# SW6208_A_A_B_C_L_LED__188.net
KiCad netlist of a schematic drawn in Altium Designer
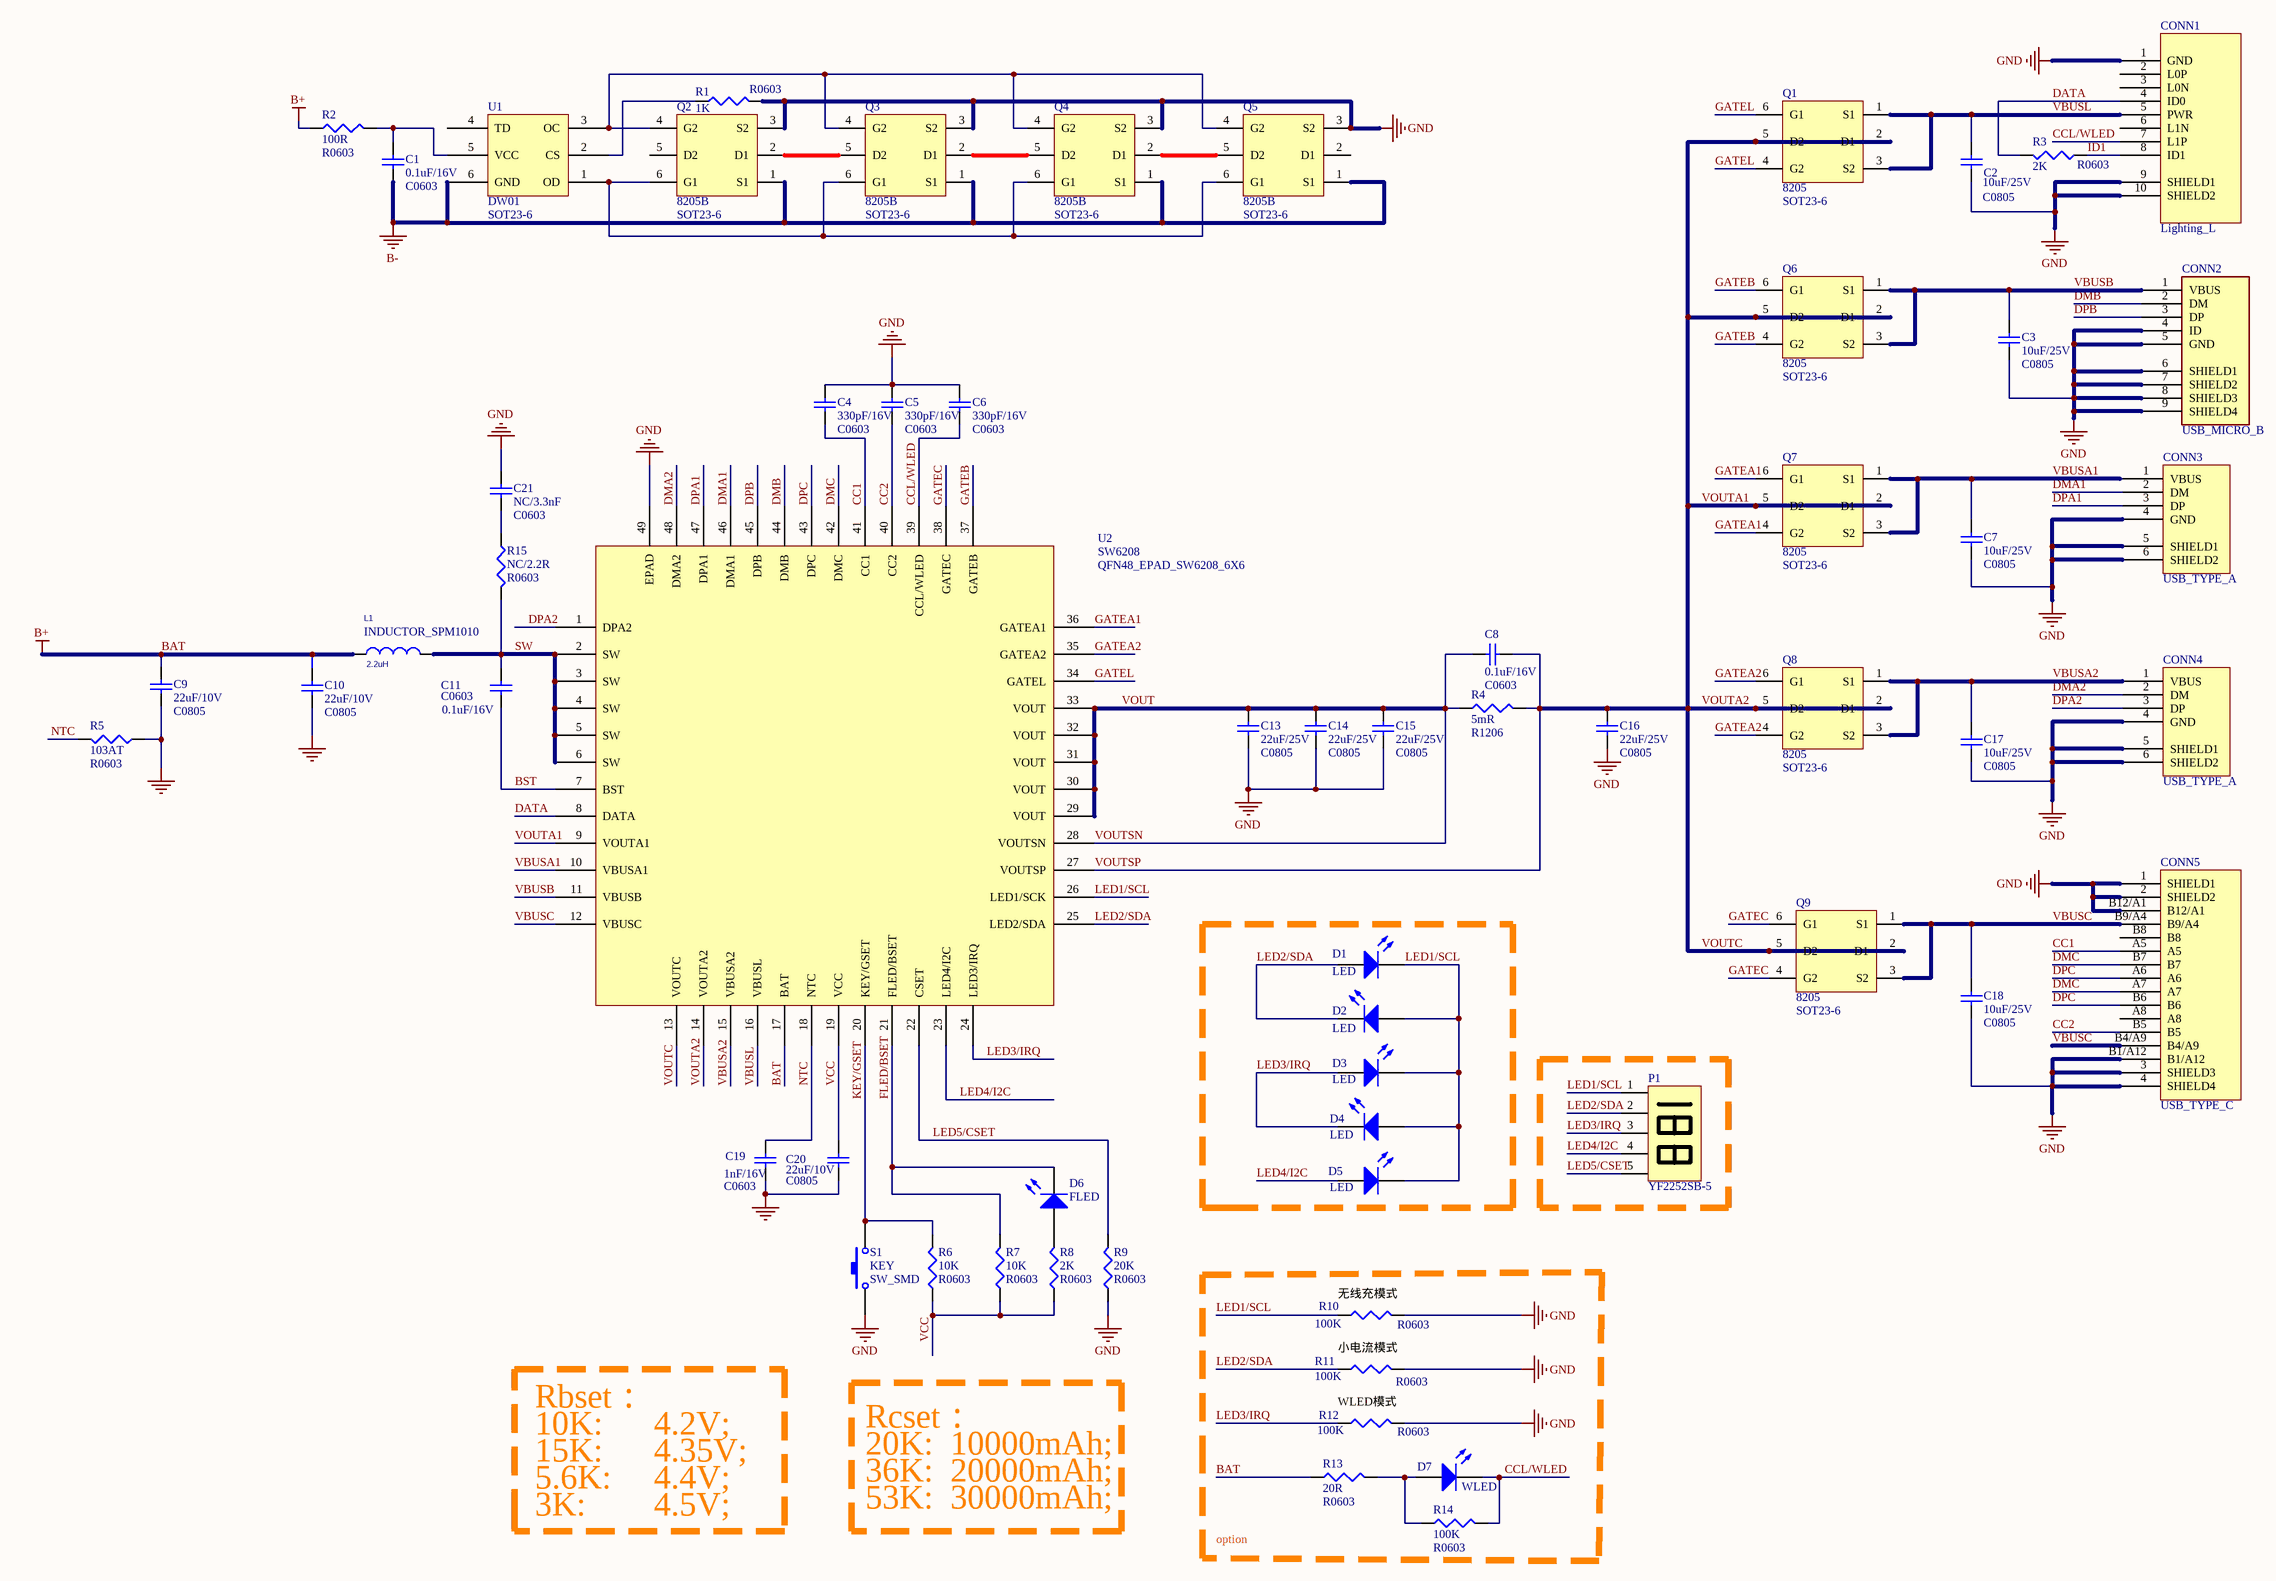
[diagram p0: SW6208+A+A+B+C+L+LED_普通188数码管.SchDoc]

(export (version "E")
  (design (tool "Eeschema 10.0.6"))
  (components
    (comp (ref "C1")
      (value "0.1uF/16V")
      (footprint "C0603")
      (description "Capacitor")
      (fields (field (name "PUBLISHER") "Altium Limited"))
      (libsource (lib "参考设计器件原理图更新") (part "CAP0603"))
    )
    (comp (ref "C2")
      (value "10uF/25V")
      (footprint "C0805")
      (description "Capacitor")
      (fields (field (name "PUBLISHER") "Altium Limited"))
      (libsource (lib "参考设计器件原理图更新") (part "CAP0805"))
    )
    (comp (ref "C3")
      (value "10uF/25V")
      (footprint "C0805")
      (description "Capacitor")
      (fields (field (name "PUBLISHER") "Altium Limited"))
      (libsource (lib "参考设计器件原理图更新") (part "CAP0805"))
    )
    (comp (ref "C4")
      (value "330pF/16V")
      (footprint "C0603")
      (description "Capacitor")
      (fields (field (name "PUBLISHER") "Altium Limited"))
      (libsource (lib "参考设计器件原理图更新") (part "CAP0603"))
    )
    (comp (ref "C5")
      (value "330pF/16V")
      (footprint "C0603")
      (description "Capacitor")
      (fields (field (name "PUBLISHER") "Altium Limited"))
      (libsource (lib "参考设计器件原理图更新") (part "CAP0603"))
    )
    (comp (ref "C6")
      (value "330pF/16V")
      (footprint "C0603")
      (description "Capacitor")
      (fields (field (name "PUBLISHER") "Altium Limited"))
      (libsource (lib "参考设计器件原理图更新") (part "CAP0603"))
    )
    (comp (ref "C7")
      (value "10uF/25V")
      (footprint "C0805")
      (description "Capacitor")
      (fields (field (name "PUBLISHER") "Altium Limited"))
      (libsource (lib "参考设计器件原理图更新") (part "CAP0805"))
    )
    (comp (ref "C8")
      (value "0.1uF/16V")
      (footprint "C0603")
      (description "Capacitor")
      (fields (field (name "PUBLISHER") "Altium Limited"))
      (libsource (lib "参考设计器件原理图更新") (part "CAP0603"))
    )
    (comp (ref "C9")
      (value "22uF/10V")
      (footprint "C0805")
      (description "Capacitor")
      (fields (field (name "PUBLISHER") "Altium Limited"))
      (libsource (lib "参考设计器件原理图更新") (part "CAP0805"))
    )
    (comp (ref "C10")
      (value "22uF/10V")
      (footprint "C0805")
      (description "Capacitor")
      (fields (field (name "PUBLISHER") "Altium Limited"))
      (libsource (lib "参考设计器件原理图更新") (part "CAP0805"))
    )
    (comp (ref "C11")
      (value "0.1uF/16V")
      (footprint "C0603")
      (description "Capacitor")
      (fields (field (name "PUBLISHER") "Altium Limited"))
      (libsource (lib "参考设计器件原理图更新") (part "CAP0603"))
    )
    (comp (ref "C13")
      (value "22uF/25V")
      (footprint "C0805")
      (description "Capacitor")
      (fields (field (name "PUBLISHER") "Altium Limited"))
      (libsource (lib "参考设计器件原理图更新") (part "CAP0805"))
    )
    (comp (ref "C14")
      (value "22uF/25V")
      (footprint "C0805")
      (description "Capacitor")
      (fields (field (name "PUBLISHER") "Altium Limited"))
      (libsource (lib "参考设计器件原理图更新") (part "CAP0805"))
    )
    (comp (ref "C15")
      (value "22uF/25V")
      (footprint "C0805")
      (description "Capacitor")
      (fields (field (name "PUBLISHER") "Altium Limited"))
      (libsource (lib "参考设计器件原理图更新") (part "CAP0805"))
    )
    (comp (ref "C16")
      (value "22uF/25V")
      (footprint "C0805")
      (description "Capacitor")
      (fields (field (name "PUBLISHER") "Altium Limited"))
      (libsource (lib "参考设计器件原理图更新") (part "CAP0805"))
    )
    (comp (ref "C17")
      (value "10uF/25V")
      (footprint "C0805")
      (description "Capacitor")
      (fields (field (name "PUBLISHER") "Altium Limited"))
      (libsource (lib "参考设计器件原理图更新") (part "CAP0805"))
    )
    (comp (ref "C18")
      (value "10uF/25V")
      (footprint "C0805")
      (description "Capacitor")
      (fields (field (name "PUBLISHER") "Altium Limited"))
      (libsource (lib "参考设计器件原理图更新") (part "CAP0805"))
    )
    (comp (ref "C19")
      (value "1nF/16V")
      (footprint "C0603")
      (description "Capacitor")
      (fields (field (name "PUBLISHER") "Altium Limited"))
      (libsource (lib "参考设计器件原理图更新") (part "CAP0603"))
    )
    (comp (ref "C20")
      (value "22uF/10V")
      (footprint "C0805")
      (description "Capacitor")
      (fields (field (name "PUBLISHER") "Altium Limited"))
      (libsource (lib "参考设计器件原理图更新") (part "CAP0805"))
    )
    (comp (ref "C21")
      (value "NC/3.3nF")
      (footprint "C0603")
      (description "Capacitor")
      (fields (field (name "PUBLISHER") "Altium Limited"))
      (libsource (lib "参考设计器件原理图更新") (part "CAP0603"))
    )
    (comp (ref "CONN1")
      (value "Lighting_L")
      (footprint "Lighting")
      (libsource (lib "参考设计器件原理图更新") (part "LIGHTING_PORT"))
    )
    (comp (ref "CONN2")
      (value "USB_MICRO_B")
      (footprint "USB_MICRO_B")
      (libsource (lib "参考设计器件原理图更新") (part "USB_MICRO_B"))
    )
    (comp (ref "CONN3")
      (value "USB_TYPE_A")
      (footprint "USB_TYPE_A")
      (libsource (lib "参考设计器件原理图更新") (part "USB_TYPE_A"))
    )
    (comp (ref "CONN4")
      (value "USB_TYPE_A")
      (footprint "USB_TYPE_A")
      (libsource (lib "参考设计器件原理图更新") (part "USB_TYPE_A"))
    )
    (comp (ref "CONN5")
      (value "USB_TYPE_C")
      (footprint "LOUISAD:USB_TYPE_C")
      (libsource (lib "参考设计器件原理图更新") (part "USB_TYPE_C"))
    )
    (comp (ref "D1")
      (value "LED")
      (footprint "LED0603")
      (fields (field (name "PUBLISHER") "Altium Limited"))
      (libsource (lib "参考设计器件原理图更新") (part "LED_0603"))
    )
    (comp (ref "D2")
      (value "LED")
      (footprint "LED0603")
      (fields (field (name "PUBLISHER") "Altium Limited"))
      (libsource (lib "参考设计器件原理图更新") (part "LED_0603"))
    )
    (comp (ref "D3")
      (value "LED")
      (footprint "LED0603")
      (fields (field (name "PUBLISHER") "Altium Limited"))
      (libsource (lib "参考设计器件原理图更新") (part "LED_0603"))
    )
    (comp (ref "D4")
      (value "LED")
      (footprint "LED0603")
      (fields (field (name "PUBLISHER") "Altium Limited"))
      (libsource (lib "参考设计器件原理图更新") (part "LED_0603"))
    )
    (comp (ref "D5")
      (value "LED")
      (footprint "LED0603")
      (fields (field (name "PUBLISHER") "Altium Limited"))
      (libsource (lib "参考设计器件原理图更新") (part "LED_0603"))
    )
    (comp (ref "D6")
      (value "FLED")
      (footprint "LED0603")
      (description "LED")
      (fields (field (name "PUBLISHER") "Altium Limited"))
      (libsource (lib "参考设计器件原理图更新") (part "LED_0603"))
    )
    (comp (ref "D7")
      (value "WLED")
      (footprint "LED_5MM")
      (fields (field (name "PUBLISHER") "Altium Limited"))
      (libsource (lib "参考设计器件原理图更新") (part "WLED"))
    )
    (comp (ref "L1")
      (value "2.2uH")
      (footprint "INDUCTOR_SPM1010")
      (description "INDUCTOR")
      (libsource (lib "参考设计器件原理图更新") (part "INDUCTOR_SPM1010"))
    )
    (comp (ref "P1")
      (value "YF2252SB-5")
      (footprint "LED_Display_5")
      (description "188_LED_Display")
      (libsource (lib "参考设计器件原理图更新") (part "LED_Display_5"))
    )
    (comp (ref "Q1")
      (value "8205")
      (footprint "SOT23-6")
      (description "NMOS")
      (fields (field (name "FOOTPRINF") "SOT23-6"))
      (libsource (lib "") (part "8205_1"))
    )
    (comp (ref "Q2")
      (value "8205B")
      (footprint "SOT23-6")
      (description "NMOS")
      (fields (field (name "FOOTPRINF") "SOT23-6"))
      (libsource (lib "参考设计器件原理图更新") (part "8205"))
    )
    (comp (ref "Q3")
      (value "8205B")
      (footprint "SOT23-6")
      (description "NMOS")
      (fields (field (name "FOOTPRINF") "SOT23-6"))
      (libsource (lib "参考设计器件原理图更新") (part "8205"))
    )
    (comp (ref "Q4")
      (value "8205B")
      (footprint "SOT23-6")
      (description "NMOS")
      (fields (field (name "FOOTPRINF") "SOT23-6"))
      (libsource (lib "参考设计器件原理图更新") (part "8205"))
    )
    (comp (ref "Q5")
      (value "8205B")
      (footprint "SOT23-6")
      (description "NMOS")
      (fields (field (name "FOOTPRINF") "SOT23-6"))
      (libsource (lib "参考设计器件原理图更新") (part "8205"))
    )
    (comp (ref "Q6")
      (value "8205")
      (footprint "SOT23-6")
      (description "NMOS")
      (fields (field (name "FOOTPRINF") "SOT23-6"))
      (libsource (lib "") (part "8205_1"))
    )
    (comp (ref "Q7")
      (value "8205")
      (footprint "SOT23-6")
      (description "NMOS")
      (fields (field (name "FOOTPRINF") "SOT23-6"))
      (libsource (lib "") (part "8205_1"))
    )
    (comp (ref "Q8")
      (value "8205")
      (footprint "SOT23-6")
      (description "NMOS")
      (fields (field (name "FOOTPRINF") "SOT23-6"))
      (libsource (lib "") (part "8205_1"))
    )
    (comp (ref "Q9")
      (value "8205")
      (footprint "SOT23-6")
      (description "NMOS")
      (fields (field (name "FOOTPRINF") "SOT23-6"))
      (libsource (lib "") (part "8205_1"))
    )
    (comp (ref "R1")
      (value "1K")
      (footprint "R0603")
      (description "Resistor")
      (fields (field (name "PUBLISHER") "Altium Limited"))
      (libsource (lib "参考设计器件原理图更新") (part "RES_0603"))
    )
    (comp (ref "R2")
      (value "100R")
      (footprint "R0603")
      (description "Resistor")
      (fields (field (name "PUBLISHER") "Altium Limited"))
      (libsource (lib "参考设计器件原理图更新") (part "RES_0603"))
    )
    (comp (ref "R3")
      (value "2K")
      (footprint "R0603")
      (description "Resistor")
      (fields (field (name "PUBLISHER") "Altium Limited"))
      (libsource (lib "参考设计器件原理图更新") (part "RES_0603"))
    )
    (comp (ref "R4")
      (value "5mR")
      (footprint "R1206")
      (description "Resistor")
      (fields (field (name "PUBLISHER") "Altium Limited"))
      (libsource (lib "参考设计器件原理图更新") (part "RES_1206"))
    )
    (comp (ref "R5")
      (value "103AT")
      (footprint "R0603")
      (description "Resistor")
      (fields (field (name "PUBLISHER") "Altium Limited"))
      (libsource (lib "参考设计器件原理图更新") (part "RES_0603"))
    )
    (comp (ref "R6")
      (value "10K")
      (footprint "R0603")
      (description "Resistor")
      (fields (field (name "PUBLISHER") "Altium Limited"))
      (libsource (lib "参考设计器件原理图更新") (part "RES_0603"))
    )
    (comp (ref "R7")
      (value "10K")
      (footprint "R0603")
      (description "Resistor")
      (fields (field (name "PUBLISHER") "Altium Limited"))
      (libsource (lib "参考设计器件原理图更新") (part "RES_0603"))
    )
    (comp (ref "R8")
      (value "2K")
      (footprint "R0603")
      (description "Resistor")
      (fields (field (name "PUBLISHER") "Altium Limited"))
      (libsource (lib "参考设计器件原理图更新") (part "RES_0603"))
    )
    (comp (ref "R9")
      (value "20K")
      (footprint "R0603")
      (description "Resistor")
      (fields (field (name "PUBLISHER") "Altium Limited"))
      (libsource (lib "参考设计器件原理图更新") (part "RES_0603"))
    )
    (comp (ref "R10")
      (value "100K")
      (footprint "R0603")
      (description "Resistor")
      (fields (field (name "PUBLISHER") "Altium Limited"))
      (libsource (lib "参考设计器件原理图更新") (part "RES_0603"))
    )
    (comp (ref "R11")
      (value "100K")
      (footprint "R0603")
      (description "Resistor")
      (fields (field (name "PUBLISHER") "Altium Limited"))
      (libsource (lib "参考设计器件原理图更新") (part "RES_0603"))
    )
    (comp (ref "R12")
      (value "100K")
      (footprint "R0603")
      (description "Resistor")
      (fields (field (name "PUBLISHER") "Altium Limited"))
      (libsource (lib "参考设计器件原理图更新") (part "RES_0603"))
    )
    (comp (ref "R13")
      (value "20R")
      (footprint "R0603")
      (description "Resistor")
      (fields (field (name "PUBLISHER") "Altium Limited"))
      (libsource (lib "参考设计器件原理图更新") (part "RES_0603"))
    )
    (comp (ref "R14")
      (value "100K")
      (footprint "R0603")
      (description "Resistor")
      (fields (field (name "PUBLISHER") "Altium Limited"))
      (libsource (lib "参考设计器件原理图更新") (part "RES_0603"))
    )
    (comp (ref "R15")
      (value "NC/2.2R")
      (footprint "R0603")
      (description "Resistor")
      (fields (field (name "PUBLISHER") "Altium Limited"))
      (libsource (lib "参考设计器件原理图更新") (part "RES_0603"))
    )
    (comp (ref "S1")
      (value "KEY")
      (footprint "SW_SMD")
      (fields (field (name "FOOTPRINF") "SW_SMD"))
      (libsource (lib "参考设计器件原理图更新") (part "SW K"))
    )
    (comp (ref "U1")
      (value "DW01")
      (footprint "SOT23-6")
      (description "BAT_PROTECT_IC")
      (libsource (lib "参考设计器件原理图更新") (part "DW01"))
    )
    (comp (ref "U2")
      (value "SW6208")
      (footprint "QFN48_EPAD_SW6208_6X6")
      (description "IC")
      (libsource (lib "芯片型号原理图") (part "SW6208"))
    )
  )
  (nets
    (net (code "1") (name "/BST") (class "Default")
      (node (ref "C11") (pin "1") (pinfunction "1_1") (pintype "passive"))
      (node (ref "U2") (pin "7") (pinfunction "BST_7") (pintype "passive"))
    )
    (net (code "2") (name "/CC1") (class "Default")
      (node (ref "C4") (pin "1") (pinfunction "1_1") (pintype "passive"))
      (node (ref "CONN5") (pin "A5") (pinfunction "A5_A5") (pintype "passive"))
      (node (ref "U2") (pin "41") (pinfunction "CC1_41") (pintype "passive"))
    )
    (net (code "3") (name "/CC2") (class "Default")
      (node (ref "C5") (pin "1") (pinfunction "1_1") (pintype "passive"))
      (node (ref "CONN5") (pin "B5") (pinfunction "B5_B5") (pintype "passive"))
      (node (ref "U2") (pin "40") (pinfunction "CC2_40") (pintype "passive"))
    )
    (net (code "4") (name "/CCL{slash}WLED") (class "Default")
      (node (ref "C6") (pin "1") (pinfunction "1_1") (pintype "passive"))
      (node (ref "CONN1") (pin "7") (pinfunction "L1P_7") (pintype "passive"))
      (node (ref "D7") (pin "2") (pinfunction "K_2") (pintype "passive"))
      (node (ref "R14") (pin "2") (pinfunction "2_2") (pintype "passive"))
      (node (ref "U2") (pin "39") (pinfunction "CCL/WLED_39") (pintype "passive"))
    )
    (net (code "5") (name "/DATA") (class "Default")
      (node (ref "CONN1") (pin "4") (pinfunction "ID0_4") (pintype "passive"))
      (node (ref "R3") (pin "2") (pinfunction "2_2") (pintype "passive"))
      (node (ref "U2") (pin "8") (pinfunction "DATA_8") (pintype "passive"))
    )
    (net (code "6") (name "/DMA1") (class "Default")
      (node (ref "CONN3") (pin "2") (pinfunction "DM_2") (pintype "passive"))
      (node (ref "U2") (pin "46") (pinfunction "DMA1_46") (pintype "passive"))
    )
    (net (code "7") (name "/DMA2") (class "Default")
      (node (ref "CONN4") (pin "2") (pinfunction "DM_2") (pintype "passive"))
      (node (ref "U2") (pin "48") (pinfunction "DMA2_48") (pintype "passive"))
    )
    (net (code "8") (name "/DMB") (class "Default")
      (node (ref "CONN2") (pin "2") (pinfunction "DM_2") (pintype "passive"))
      (node (ref "U2") (pin "44") (pinfunction "DMB_44") (pintype "passive"))
    )
    (net (code "9") (name "/DMC") (class "Default")
      (node (ref "CONN5") (pin "A7") (pinfunction "A7_A7") (pintype "passive"))
      (node (ref "CONN5") (pin "B7") (pinfunction "B7_B7") (pintype "passive"))
      (node (ref "U2") (pin "42") (pinfunction "DMC_42") (pintype "passive"))
    )
    (net (code "10") (name "/DPA1") (class "Default")
      (node (ref "CONN3") (pin "3") (pinfunction "DP_3") (pintype "passive"))
      (node (ref "U2") (pin "47") (pinfunction "DPA1_47") (pintype "passive"))
    )
    (net (code "11") (name "/DPA2") (class "Default")
      (node (ref "CONN4") (pin "3") (pinfunction "DP_3") (pintype "passive"))
      (node (ref "U2") (pin "1") (pinfunction "DPA2_1") (pintype "passive"))
    )
    (net (code "12") (name "/DPB") (class "Default")
      (node (ref "CONN2") (pin "3") (pinfunction "DP_3") (pintype "passive"))
      (node (ref "U2") (pin "45") (pinfunction "DPB_45") (pintype "passive"))
    )
    (net (code "13") (name "/DPC") (class "Default")
      (node (ref "CONN5") (pin "A6") (pinfunction "A6_A6") (pintype "passive"))
      (node (ref "CONN5") (pin "B6") (pinfunction "B6_B6") (pintype "passive"))
      (node (ref "U2") (pin "43") (pinfunction "DPC_43") (pintype "passive"))
    )
    (net (code "14") (name "/FLED{slash}BSET") (class "Default")
      (node (ref "D6") (pin "2") (pinfunction "K_2") (pintype "passive"))
      (node (ref "R7") (pin "2") (pinfunction "2_2") (pintype "passive"))
      (node (ref "U2") (pin "21") (pinfunction "FLED/BSET_21") (pintype "passive"))
    )
    (net (code "15") (name "/GATEA1") (class "Default")
      (node (ref "Q7") (pin "4") (pinfunction "G2_4") (pintype "passive"))
      (node (ref "Q7") (pin "6") (pinfunction "G1_6") (pintype "passive"))
      (node (ref "U2") (pin "36") (pinfunction "GATEA1_36") (pintype "passive"))
    )
    (net (code "16") (name "/GATEA2") (class "Default")
      (node (ref "Q8") (pin "4") (pinfunction "G2_4") (pintype "passive"))
      (node (ref "Q8") (pin "6") (pinfunction "G1_6") (pintype "passive"))
      (node (ref "U2") (pin "35") (pinfunction "GATEA2_35") (pintype "passive"))
    )
    (net (code "17") (name "/GATEB") (class "Default")
      (node (ref "Q6") (pin "4") (pinfunction "G2_4") (pintype "passive"))
      (node (ref "Q6") (pin "6") (pinfunction "G1_6") (pintype "passive"))
      (node (ref "U2") (pin "37") (pinfunction "GATEB_37") (pintype "passive"))
    )
    (net (code "18") (name "/GATEC") (class "Default")
      (node (ref "Q9") (pin "4") (pinfunction "G2_4") (pintype "passive"))
      (node (ref "Q9") (pin "6") (pinfunction "G1_6") (pintype "passive"))
      (node (ref "U2") (pin "38") (pinfunction "GATEC_38") (pintype "passive"))
    )
    (net (code "19") (name "/GATEL") (class "Default")
      (node (ref "Q1") (pin "4") (pinfunction "G2_4") (pintype "passive"))
      (node (ref "Q1") (pin "6") (pinfunction "G1_6") (pintype "passive"))
      (node (ref "U2") (pin "34") (pinfunction "GATEL_34") (pintype "passive"))
    )
    (net (code "20") (name "/ID1") (class "Default")
      (node (ref "CONN1") (pin "8") (pinfunction "ID1_8") (pintype "passive"))
      (node (ref "R3") (pin "1") (pinfunction "1_1") (pintype "passive"))
    )
    (net (code "21") (name "/KEY{slash}GSET") (class "Default")
      (node (ref "R6") (pin "2") (pinfunction "2_2") (pintype "passive"))
      (node (ref "S1") (pin "2") (pinfunction "2_2") (pintype "passive"))
      (node (ref "U2") (pin "20") (pinfunction "KEY/GSET_20") (pintype "passive"))
    )
    (net (code "22") (name "/LED1{slash}SCL") (class "Default")
      (node (ref "D1") (pin "2") (pinfunction "K_2") (pintype "passive"))
      (node (ref "D2") (pin "1") (pinfunction "A_1") (pintype "passive"))
      (node (ref "D3") (pin "2") (pinfunction "K_2") (pintype "passive"))
      (node (ref "D4") (pin "1") (pinfunction "A_1") (pintype "passive"))
      (node (ref "D5") (pin "2") (pinfunction "K_2") (pintype "passive"))
      (node (ref "P1") (pin "1") (pinfunction "F_1") (pintype "passive"))
      (node (ref "R10") (pin "1") (pinfunction "1_1") (pintype "passive"))
      (node (ref "U2") (pin "26") (pinfunction "LED1/SCK_26") (pintype "passive"))
    )
    (net (code "23") (name "/LED2{slash}SDA") (class "Default")
      (node (ref "D1") (pin "1") (pinfunction "A_1") (pintype "passive"))
      (node (ref "D2") (pin "2") (pinfunction "K_2") (pintype "passive"))
      (node (ref "P1") (pin "2") (pinfunction "C_2") (pintype "passive"))
      (node (ref "R11") (pin "1") (pinfunction "1_1") (pintype "passive"))
      (node (ref "U2") (pin "25") (pinfunction "LED2/SDA_25") (pintype "passive"))
    )
    (net (code "24") (name "/LED3{slash}IRQ") (class "Default")
      (node (ref "D3") (pin "1") (pinfunction "A_1") (pintype "passive"))
      (node (ref "D4") (pin "2") (pinfunction "K_2") (pintype "passive"))
      (node (ref "P1") (pin "3") (pinfunction "D_3") (pintype "passive"))
      (node (ref "R12") (pin "1") (pinfunction "1_1") (pintype "passive"))
      (node (ref "U2") (pin "24") (pinfunction "LED3/IRQ_24") (pintype "passive"))
    )
    (net (code "25") (name "/LED4{slash}I2C") (class "Default")
      (node (ref "D5") (pin "1") (pinfunction "A_1") (pintype "passive"))
      (node (ref "P1") (pin "4") (pinfunction "E_4") (pintype "passive"))
      (node (ref "U2") (pin "23") (pinfunction "LED4/I2C_23") (pintype "passive"))
    )
    (net (code "26") (name "/LED5{slash}CSET") (class "Default")
      (node (ref "P1") (pin "5") (pinfunction "G_5") (pintype "passive"))
      (node (ref "R9") (pin "2") (pinfunction "2_2") (pintype "passive"))
      (node (ref "U2") (pin "22") (pinfunction "CSET_22") (pintype "passive"))
    )
    (net (code "27") (name "/NTC") (class "Default")
      (node (ref "C19") (pin "1") (pinfunction "1_1") (pintype "passive"))
      (node (ref "R5") (pin "2") (pinfunction "2_2") (pintype "passive"))
      (node (ref "U2") (pin "18") (pinfunction "NTC_18") (pintype "passive"))
    )
    (net (code "28") (name "/SW") (class "Default")
      (node (ref "C11") (pin "2") (pinfunction "2_2") (pintype "passive"))
      (node (ref "L1") (pin "2") (pinfunction "2_2") (pintype "passive"))
      (node (ref "R15") (pin "2") (pinfunction "2_2") (pintype "passive"))
      (node (ref "U2") (pin "2") (pinfunction "SW_2") (pintype "passive"))
      (node (ref "U2") (pin "3") (pinfunction "SW_3") (pintype "passive"))
      (node (ref "U2") (pin "4") (pinfunction "SW_4") (pintype "passive"))
      (node (ref "U2") (pin "5") (pinfunction "SW_5") (pintype "passive"))
      (node (ref "U2") (pin "6") (pinfunction "SW_6") (pintype "passive"))
    )
    (net (code "29") (name "/VBUSA1") (class "Default")
      (node (ref "C7") (pin "2") (pinfunction "2_2") (pintype "passive"))
      (node (ref "CONN3") (pin "1") (pinfunction "VBUS_1") (pintype "passive"))
      (node (ref "Q7") (pin "1") (pinfunction "S1_1") (pintype "passive"))
      (node (ref "Q7") (pin "3") (pinfunction "S2_3") (pintype "passive"))
      (node (ref "U2") (pin "10") (pinfunction "VBUSA1_10") (pintype "passive"))
    )
    (net (code "30") (name "/VBUSA2") (class "Default")
      (node (ref "C17") (pin "2") (pinfunction "2_2") (pintype "passive"))
      (node (ref "CONN4") (pin "1") (pinfunction "VBUS_1") (pintype "passive"))
      (node (ref "Q8") (pin "1") (pinfunction "S1_1") (pintype "passive"))
      (node (ref "Q8") (pin "3") (pinfunction "S2_3") (pintype "passive"))
      (node (ref "U2") (pin "15") (pinfunction "VBUSA2_15") (pintype "passive"))
    )
    (net (code "31") (name "/VBUSB") (class "Default")
      (node (ref "C3") (pin "2") (pinfunction "2_2") (pintype "passive"))
      (node (ref "CONN2") (pin "1") (pinfunction "VBUS_1") (pintype "passive"))
      (node (ref "Q6") (pin "1") (pinfunction "S1_1") (pintype "passive"))
      (node (ref "Q6") (pin "3") (pinfunction "S2_3") (pintype "passive"))
      (node (ref "U2") (pin "11") (pinfunction "VBUSB_11") (pintype "passive"))
    )
    (net (code "32") (name "/VBUSC") (class "Default")
      (node (ref "C18") (pin "2") (pinfunction "2_2") (pintype "passive"))
      (node (ref "CONN5") (pin "B4/A9") (pinfunction "B4/A9_B4/A9") (pintype "passive"))
      (node (ref "CONN5") (pin "B9/A4") (pinfunction "B9/A4_B9/A4") (pintype "passive"))
      (node (ref "Q9") (pin "1") (pinfunction "S1_1") (pintype "passive"))
      (node (ref "Q9") (pin "3") (pinfunction "S2_3") (pintype "passive"))
      (node (ref "U2") (pin "12") (pinfunction "VBUSC_12") (pintype "passive"))
    )
    (net (code "33") (name "/VBUSL") (class "Default")
      (node (ref "C2") (pin "2") (pinfunction "2_2") (pintype "passive"))
      (node (ref "CONN1") (pin "5") (pinfunction "PWR_5") (pintype "passive"))
      (node (ref "Q1") (pin "1") (pinfunction "S1_1") (pintype "passive"))
      (node (ref "Q1") (pin "3") (pinfunction "S2_3") (pintype "passive"))
      (node (ref "U2") (pin "16") (pinfunction "VBUSL_16") (pintype "passive"))
    )
    (net (code "34") (name "/VCC") (class "Default")
      (node (ref "C20") (pin "1") (pinfunction "1_1") (pintype "passive"))
      (node (ref "R6") (pin "1") (pinfunction "1_1") (pintype "passive"))
      (node (ref "R7") (pin "1") (pinfunction "1_1") (pintype "passive"))
      (node (ref "R8") (pin "1") (pinfunction "1_1") (pintype "passive"))
      (node (ref "U2") (pin "19") (pinfunction "VCC_19") (pintype "passive"))
    )
    (net (code "35") (name "/VOUT") (class "Default")
      (node (ref "C13") (pin "2") (pinfunction "2_2") (pintype "passive"))
      (node (ref "C14") (pin "2") (pinfunction "2_2") (pintype "passive"))
      (node (ref "C15") (pin "2") (pinfunction "2_2") (pintype "passive"))
      (node (ref "C8") (pin "1") (pinfunction "1_1") (pintype "passive"))
      (node (ref "R4") (pin "1") (pinfunction "1_1") (pintype "passive"))
      (node (ref "U2") (pin "28") (pinfunction "VOUTSN_28") (pintype "passive"))
      (node (ref "U2") (pin "29") (pinfunction "VOUT_29") (pintype "passive"))
      (node (ref "U2") (pin "30") (pinfunction "VOUT_30") (pintype "passive"))
      (node (ref "U2") (pin "31") (pinfunction "VOUT_31") (pintype "passive"))
      (node (ref "U2") (pin "32") (pinfunction "VOUT_32") (pintype "passive"))
      (node (ref "U2") (pin "33") (pinfunction "VOUT_33") (pintype "passive"))
    )
    (net (code "36") (name "/VOUTA1") (class "Default")
      (node (ref "C16") (pin "2") (pinfunction "2_2") (pintype "passive"))
      (node (ref "C8") (pin "2") (pinfunction "2_2") (pintype "passive"))
      (node (ref "Q1") (pin "2") (pinfunction "D1_2") (pintype "passive"))
      (node (ref "Q1") (pin "5") (pinfunction "D2_5") (pintype "passive"))
      (node (ref "Q6") (pin "2") (pinfunction "D1_2") (pintype "passive"))
      (node (ref "Q6") (pin "5") (pinfunction "D2_5") (pintype "passive"))
      (node (ref "Q7") (pin "2") (pinfunction "D1_2") (pintype "passive"))
      (node (ref "Q7") (pin "5") (pinfunction "D2_5") (pintype "passive"))
      (node (ref "Q8") (pin "2") (pinfunction "D1_2") (pintype "passive"))
      (node (ref "Q8") (pin "5") (pinfunction "D2_5") (pintype "passive"))
      (node (ref "Q9") (pin "2") (pinfunction "D1_2") (pintype "passive"))
      (node (ref "Q9") (pin "5") (pinfunction "D2_5") (pintype "passive"))
      (node (ref "R4") (pin "2") (pinfunction "2_2") (pintype "passive"))
      (node (ref "U2") (pin "13") (pinfunction "VOUTC_13") (pintype "passive"))
      (node (ref "U2") (pin "14") (pinfunction "VOUTA2_14") (pintype "passive"))
      (node (ref "U2") (pin "27") (pinfunction "VOUTSP_27") (pintype "passive"))
      (node (ref "U2") (pin "9") (pinfunction "VOUTA1_9") (pintype "passive"))
    )
    (net (code "37") (name "B+") (class "Default")
      (node (ref "C10") (pin "2") (pinfunction "2_2") (pintype "passive"))
      (node (ref "C9") (pin "2") (pinfunction "2_2") (pintype "passive"))
      (node (ref "L1") (pin "1") (pinfunction "1_1") (pintype "passive"))
      (node (ref "R13") (pin "1") (pinfunction "1_1") (pintype "passive"))
      (node (ref "R2") (pin "1") (pinfunction "1_1") (pintype "passive"))
      (node (ref "U2") (pin "17") (pinfunction "BAT_17") (pintype "passive"))
    )
    (net (code "38") (name "B-") (class "Default")
      (node (ref "C1") (pin "1") (pinfunction "1_1") (pintype "passive"))
      (node (ref "Q2") (pin "1") (pinfunction "S1_1") (pintype "passive"))
      (node (ref "Q3") (pin "1") (pinfunction "S1_1") (pintype "passive"))
      (node (ref "Q4") (pin "1") (pinfunction "S1_1") (pintype "passive"))
      (node (ref "Q5") (pin "1") (pinfunction "S1_1") (pintype "passive"))
      (node (ref "U1") (pin "6") (pinfunction "GND_6") (pintype "passive"))
    )
    (net (code "39") (name "GND") (class "Default")
      (node (ref "C10") (pin "1") (pinfunction "1_1") (pintype "passive"))
      (node (ref "C13") (pin "1") (pinfunction "1_1") (pintype "passive"))
      (node (ref "C14") (pin "1") (pinfunction "1_1") (pintype "passive"))
      (node (ref "C15") (pin "1") (pinfunction "1_1") (pintype "passive"))
      (node (ref "C16") (pin "1") (pinfunction "1_1") (pintype "passive"))
      (node (ref "C17") (pin "1") (pinfunction "1_1") (pintype "passive"))
      (node (ref "C18") (pin "1") (pinfunction "1_1") (pintype "passive"))
      (node (ref "C19") (pin "2") (pinfunction "2_2") (pintype "passive"))
      (node (ref "C2") (pin "1") (pinfunction "1_1") (pintype "passive"))
      (node (ref "C20") (pin "2") (pinfunction "2_2") (pintype "passive"))
      (node (ref "C21") (pin "2") (pinfunction "2_2") (pintype "passive"))
      (node (ref "C3") (pin "1") (pinfunction "1_1") (pintype "passive"))
      (node (ref "C4") (pin "2") (pinfunction "2_2") (pintype "passive"))
      (node (ref "C5") (pin "2") (pinfunction "2_2") (pintype "passive"))
      (node (ref "C6") (pin "2") (pinfunction "2_2") (pintype "passive"))
      (node (ref "C7") (pin "1") (pinfunction "1_1") (pintype "passive"))
      (node (ref "C9") (pin "1") (pinfunction "1_1") (pintype "passive"))
      (node (ref "CONN1") (pin "1") (pinfunction "GND_1") (pintype "passive"))
      (node (ref "CONN1") (pin "10") (pinfunction "SHIELD2_10") (pintype "passive"))
      (node (ref "CONN1") (pin "9") (pinfunction "SHIELD1_9") (pintype "passive"))
      (node (ref "CONN2") (pin "4") (pinfunction "ID_4") (pintype "passive"))
      (node (ref "CONN2") (pin "5") (pinfunction "GND_5") (pintype "passive"))
      (node (ref "CONN2") (pin "6") (pinfunction "SHIELD1_6") (pintype "passive"))
      (node (ref "CONN2") (pin "7") (pinfunction "SHIELD2_7") (pintype "passive"))
      (node (ref "CONN2") (pin "8") (pinfunction "SHIELD3_8") (pintype "passive"))
      (node (ref "CONN2") (pin "9") (pinfunction "SHIELD4_9") (pintype "passive"))
      (node (ref "CONN3") (pin "4") (pinfunction "GND_4") (pintype "passive"))
      (node (ref "CONN3") (pin "5") (pinfunction "SHIELD1_5") (pintype "passive"))
      (node (ref "CONN3") (pin "6") (pinfunction "SHIELD2_6") (pintype "passive"))
      (node (ref "CONN4") (pin "4") (pinfunction "GND_4") (pintype "passive"))
      (node (ref "CONN4") (pin "5") (pinfunction "SHIELD1_5") (pintype "passive"))
      (node (ref "CONN4") (pin "6") (pinfunction "SHIELD2_6") (pintype "passive"))
      (node (ref "CONN5") (pin "1") (pinfunction "SHIELD1_1") (pintype "passive"))
      (node (ref "CONN5") (pin "2") (pinfunction "SHIELD2_2") (pintype "passive"))
      (node (ref "CONN5") (pin "3") (pinfunction "SHIELD3_3") (pintype "passive"))
      (node (ref "CONN5") (pin "4") (pinfunction "SHIELD4_4") (pintype "passive"))
      (node (ref "CONN5") (pin "B1/A12") (pinfunction "B1/A12_B1/A12") (pintype "passive"))
      (node (ref "CONN5") (pin "B12/A1") (pinfunction "B12/A1_B12/A1") (pintype "passive"))
      (node (ref "Q2") (pin "3") (pinfunction "S2_3") (pintype "passive"))
      (node (ref "Q3") (pin "3") (pinfunction "S2_3") (pintype "passive"))
      (node (ref "Q4") (pin "3") (pinfunction "S2_3") (pintype "passive"))
      (node (ref "Q5") (pin "3") (pinfunction "S2_3") (pintype "passive"))
      (node (ref "R1") (pin "2") (pinfunction "2_2") (pintype "passive"))
      (node (ref "R10") (pin "2") (pinfunction "2_2") (pintype "passive"))
      (node (ref "R11") (pin "2") (pinfunction "2_2") (pintype "passive"))
      (node (ref "R12") (pin "2") (pinfunction "2_2") (pintype "passive"))
      (node (ref "R5") (pin "1") (pinfunction "1_1") (pintype "passive"))
      (node (ref "R9") (pin "1") (pinfunction "1_1") (pintype "passive"))
      (node (ref "S1") (pin "1") (pinfunction "1_1") (pintype "passive"))
      (node (ref "U2") (pin "49") (pinfunction "EPAD_49") (pintype "passive"))
    )
    (net (code "40") (name "Net-(C21-Pad1)") (class "Default")
      (node (ref "C21") (pin "1") (pinfunction "1_1") (pintype "passive"))
      (node (ref "R15") (pin "1") (pinfunction "1_1") (pintype "passive"))
    )
    (net (code "41") (name "Net-(D6-A)") (class "Default")
      (node (ref "D6") (pin "1") (pinfunction "A_1") (pintype "passive"))
      (node (ref "R8") (pin "2") (pinfunction "2_2") (pintype "passive"))
    )
    (net (code "42") (name "Net-(D7-A)") (class "Default")
      (node (ref "D7") (pin "1") (pinfunction "A_1") (pintype "passive"))
      (node (ref "R13") (pin "2") (pinfunction "2_2") (pintype "passive"))
      (node (ref "R14") (pin "1") (pinfunction "1_1") (pintype "passive"))
    )
    (net (code "43") (name "Net-(Q2-D1)") (class "Default")
      (node (ref "Q2") (pin "2") (pinfunction "D1_2") (pintype "passive"))
      (node (ref "Q3") (pin "5") (pinfunction "D2_5") (pintype "passive"))
    )
    (net (code "44") (name "Net-(Q2-G1)") (class "Default")
      (node (ref "Q2") (pin "6") (pinfunction "G1_6") (pintype "passive"))
      (node (ref "Q3") (pin "6") (pinfunction "G1_6") (pintype "passive"))
      (node (ref "Q4") (pin "6") (pinfunction "G1_6") (pintype "passive"))
      (node (ref "Q5") (pin "6") (pinfunction "G1_6") (pintype "passive"))
      (node (ref "U1") (pin "1") (pinfunction "OD_1") (pintype "passive"))
    )
    (net (code "45") (name "Net-(Q2-G2)") (class "Default")
      (node (ref "Q2") (pin "4") (pinfunction "G2_4") (pintype "passive"))
      (node (ref "Q3") (pin "4") (pinfunction "G2_4") (pintype "passive"))
      (node (ref "Q4") (pin "4") (pinfunction "G2_4") (pintype "passive"))
      (node (ref "Q5") (pin "4") (pinfunction "G2_4") (pintype "passive"))
      (node (ref "U1") (pin "3") (pinfunction "OC_3") (pintype "passive"))
    )
    (net (code "46") (name "Net-(Q3-D1)") (class "Default")
      (node (ref "Q3") (pin "2") (pinfunction "D1_2") (pintype "passive"))
      (node (ref "Q4") (pin "5") (pinfunction "D2_5") (pintype "passive"))
    )
    (net (code "47") (name "Net-(Q4-D1)") (class "Default")
      (node (ref "Q4") (pin "2") (pinfunction "D1_2") (pintype "passive"))
      (node (ref "Q5") (pin "5") (pinfunction "D2_5") (pintype "passive"))
    )
    (net (code "48") (name "Net-(U1-CS)") (class "Default")
      (node (ref "R1") (pin "1") (pinfunction "1_1") (pintype "passive"))
      (node (ref "U1") (pin "2") (pinfunction "CS_2") (pintype "passive"))
    )
    (net (code "49") (name "Net-(U1-VCC)") (class "Default")
      (node (ref "C1") (pin "2") (pinfunction "2_2") (pintype "passive"))
      (node (ref "R2") (pin "2") (pinfunction "2_2") (pintype "passive"))
      (node (ref "U1") (pin "5") (pinfunction "VCC_5") (pintype "passive"))
    )
    (net (code "50") (name "unconnected-(CONN1-L0N-Pad3)") (class "Default")
      (node (ref "CONN1") (pin "3") (pinfunction "L0N_3") (pintype "passive"))
    )
    (net (code "51") (name "unconnected-(CONN1-L0P-Pad2)") (class "Default")
      (node (ref "CONN1") (pin "2") (pinfunction "L0P_2") (pintype "passive"))
    )
    (net (code "52") (name "unconnected-(CONN1-L1N-Pad6)") (class "Default")
      (node (ref "CONN1") (pin "6") (pinfunction "L1N_6") (pintype "passive"))
    )
    (net (code "53") (name "unconnected-(CONN5-PadA8)") (class "Default")
      (node (ref "CONN5") (pin "A8") (pinfunction "A8_A8") (pintype "passive"))
    )
    (net (code "54") (name "unconnected-(CONN5-PadB8)") (class "Default")
      (node (ref "CONN5") (pin "B8") (pinfunction "B8_B8") (pintype "passive"))
    )
    (net (code "55") (name "unconnected-(Q2-D2-Pad5)") (class "Default")
      (node (ref "Q2") (pin "5") (pinfunction "D2_5") (pintype "passive"))
    )
    (net (code "56") (name "unconnected-(Q5-D1-Pad2)") (class "Default")
      (node (ref "Q5") (pin "2") (pinfunction "D1_2") (pintype "passive"))
    )
    (net (code "57") (name "unconnected-(U1-TD-Pad4)") (class "Default")
      (node (ref "U1") (pin "4") (pinfunction "TD_4") (pintype "passive"))
    )
  )
)
